# Main_Board.net
KiCad netlist of a schematic drawn in EAGLE
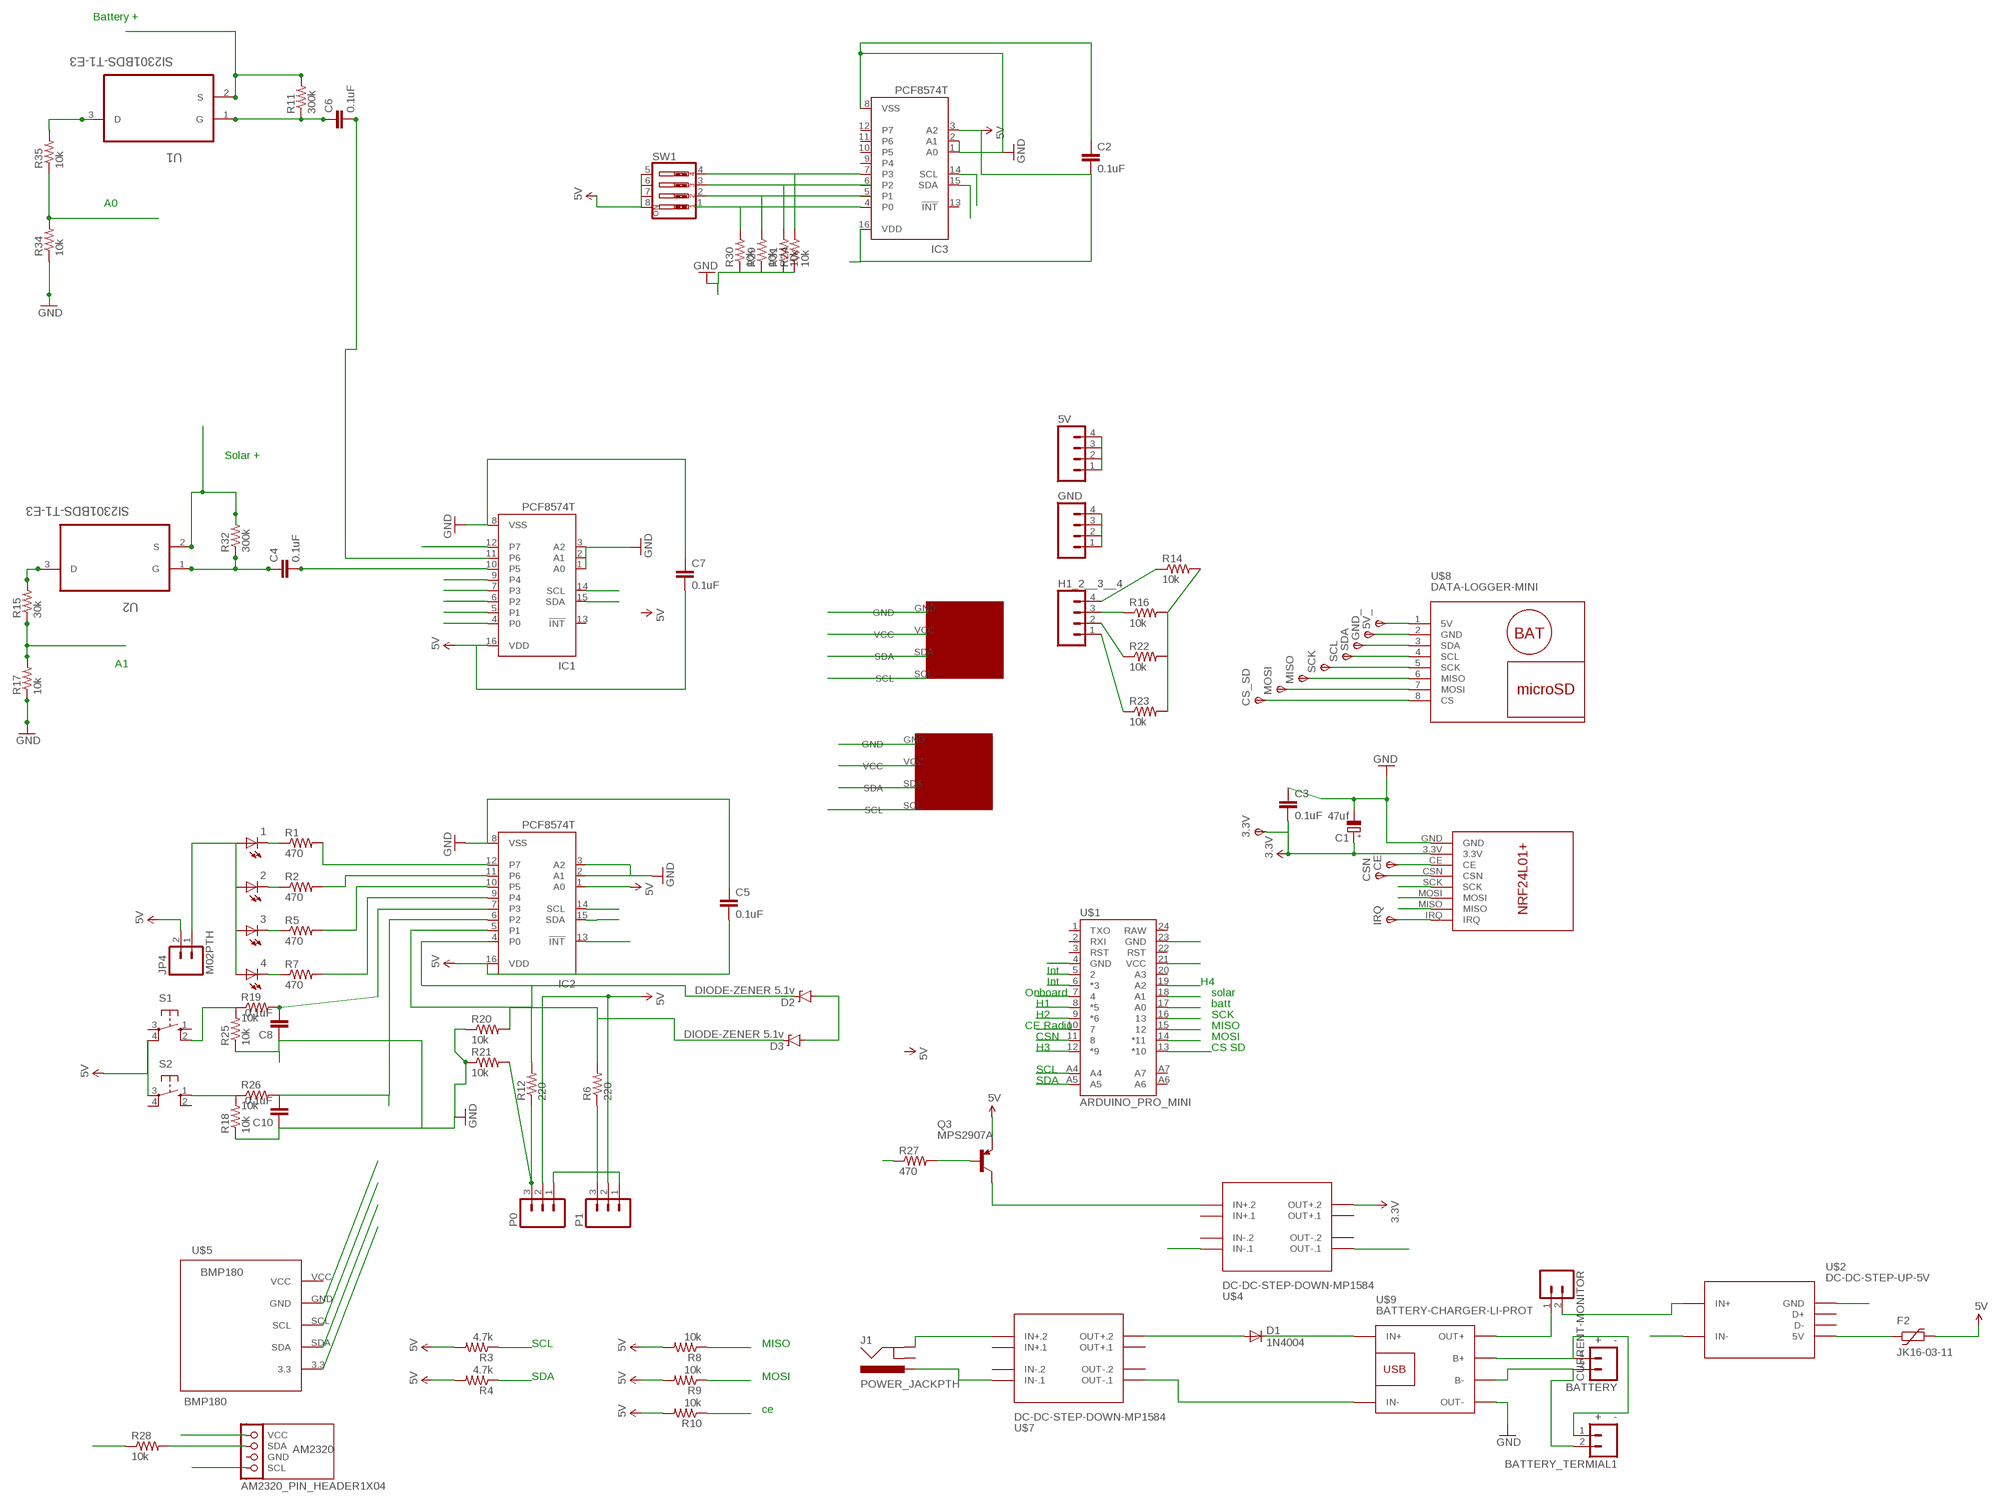
[diagram p0: schematic, sheet 1]

(export (version "E")
  (design (tool "Eeschema 10.0.6"))
  (components
    (comp (ref "1")
      (value "LED3MM")
      (footprint "eagle-import:LED3MM")
      (libsource (lib "eagle-import") (part "LED3MM"))
    )
    (comp (ref "2")
      (value "LED3MM")
      (footprint "eagle-import:LED3MM")
      (libsource (lib "eagle-import") (part "LED3MM"))
    )
    (comp (ref "3")
      (value "LED3MM")
      (footprint "eagle-import:LED3MM")
      (libsource (lib "eagle-import") (part "LED3MM"))
    )
    (comp (ref "3.3V")
      (value "TPSB1,27")
      (footprint "eagle-import:B1,27")
      (libsource (lib "eagle-import") (part "TPSB1,27"))
    )
    (comp (ref "4")
      (value "LED3MM")
      (footprint "eagle-import:LED3MM")
      (libsource (lib "eagle-import") (part "LED3MM"))
    )
    (comp (ref "5V")
      (value "M04PTH")
      (footprint "eagle-import:1X04")
      (libsource (lib "eagle-import") (part "M04PTH"))
    )
    (comp (ref "5V_")
      (value "SCK")
      (footprint "eagle-import:B1,27")
      (libsource (lib "eagle-import") (part "TPSB1,27"))
    )
    (comp (ref "AM2320")
      (value "AM2320_PIN_HEADER1X04")
      (footprint "eagle-import:1X04")
      (libsource (lib "eagle-import") (part "AM2320_PIN_HEADER1X04"))
    )
    (comp (ref "BATTERY")
      (value "+ -")
      (footprint "eagle-import:1X02")
      (libsource (lib "eagle-import") (part "M02PTH"))
    )
    (comp (ref "BATTERY_TERMIAL1")
      (value "+ -")
      (footprint "eagle-import:1X02")
      (libsource (lib "eagle-import") (part "M02PTH"))
    )
    (comp (ref "C1")
      (value "47uf")
      (footprint "eagle-import:E2,5-5")
      (libsource (lib "eagle-import") (part "CPOL-EUE2.5-5"))
    )
    (comp (ref "C2")
      (value "0.1uF")
      (footprint "eagle-import:0805")
      (libsource (lib "eagle-import") (part "2.2UF-25V-+80/-20(0805)"))
    )
    (comp (ref "C3")
      (value "0.1uF")
      (footprint "eagle-import:0805")
      (libsource (lib "eagle-import") (part "2.2UF-25V-+80/-20(0805)"))
    )
    (comp (ref "C4")
      (value "0.1uF")
      (footprint "eagle-import:0805")
      (libsource (lib "eagle-import") (part "2.2UF-25V-+80/-20(0805)"))
    )
    (comp (ref "C5")
      (value "0.1uF")
      (footprint "eagle-import:0805")
      (libsource (lib "eagle-import") (part "2.2UF-25V-+80/-20(0805)"))
    )
    (comp (ref "C6")
      (value "0.1uF")
      (footprint "eagle-import:0805")
      (libsource (lib "eagle-import") (part "2.2UF-25V-+80/-20(0805)"))
    )
    (comp (ref "C7")
      (value "0.1uF")
      (footprint "eagle-import:0805")
      (libsource (lib "eagle-import") (part "2.2UF-25V-+80/-20(0805)"))
    )
    (comp (ref "C8")
      (value "0.1uF")
      (footprint "eagle-import:0805")
      (libsource (lib "eagle-import") (part "2.2UF-25V-+80/-20(0805)"))
    )
    (comp (ref "C10")
      (value "0.1uF")
      (footprint "eagle-import:0805")
      (libsource (lib "eagle-import") (part "2.2UF-25V-+80/-20(0805)"))
    )
    (comp (ref "CE")
      (value "TPSB1,27")
      (footprint "eagle-import:B1,27")
      (libsource (lib "eagle-import") (part "TPSB1,27"))
    )
    (comp (ref "CSN")
      (value "TPSB1,27")
      (footprint "eagle-import:B1,27")
      (libsource (lib "eagle-import") (part "TPSB1,27"))
    )
    (comp (ref "CS_SD")
      (value "TPSB1,27")
      (footprint "eagle-import:B1,27")
      (libsource (lib "eagle-import") (part "TPSB1,27"))
    )
    (comp (ref "CURRENT-MONITOR")
      (value "M02PTH")
      (footprint "eagle-import:1X02")
      (libsource (lib "eagle-import") (part "M02PTH"))
    )
    (comp (ref "D1")
      (value "1N4004")
      (footprint "eagle-import:DO41-10")
      (libsource (lib "eagle-import") (part "1N4004"))
    )
    (comp (ref "D2")
      (value "DIODE-ZENER 5.1v")
      (footprint "eagle-import:DIODE-ZENER")
      (libsource (lib "eagle-import") (part "DIODE-ZENERPTH"))
    )
    (comp (ref "D3")
      (value "DIODE-ZENER 5.1v")
      (footprint "eagle-import:DIODE-ZENER")
      (libsource (lib "eagle-import") (part "DIODE-ZENERPTH"))
    )
    (comp (ref "F2")
      (value "JK16-03-11")
      (footprint "eagle-import:JK16-03-11")
      (libsource (lib "eagle-import") (part "JK16-03-11"))
    )
    (comp (ref "GND")
      (value "M04PTH")
      (footprint "eagle-import:1X04")
      (libsource (lib "eagle-import") (part "M04PTH"))
    )
    (comp (ref "GND_")
      (value "GND")
      (footprint "eagle-import:B1,27")
      (libsource (lib "eagle-import") (part "TPSB1,27"))
    )
    (comp (ref "H1_2__3__4")
      (value "M04PTH")
      (footprint "eagle-import:1X04")
      (libsource (lib "eagle-import") (part "M04PTH"))
    )
    (comp (ref "IC1")
      (value "PCF8574T")
      (footprint "eagle-import:SO16W")
      (fields (field (name "MPN") "PCF8574T/3,512"))
      (libsource (lib "eagle-import") (part "PCF8574T"))
    )
    (comp (ref "IC2")
      (value "PCF8574T")
      (footprint "eagle-import:SO16W")
      (fields (field (name "MPN") "PCF8574T/3,512"))
      (libsource (lib "eagle-import") (part "PCF8574T"))
    )
    (comp (ref "IC3")
      (value "PCF8574T")
      (footprint "eagle-import:SO16W")
      (fields (field (name "MPN") "PCF8574T/3,512"))
      (libsource (lib "eagle-import") (part "PCF8574T"))
    )
    (comp (ref "IRQ")
      (value "TPSB1,27")
      (footprint "eagle-import:B1,27")
      (libsource (lib "eagle-import") (part "TPSB1,27"))
    )
    (comp (ref "J1")
      (value "POWER_JACKPTH")
      (footprint "eagle-import:POWER_JACK_PTH")
      (libsource (lib "eagle-import") (part "POWER_JACKPTH"))
    )
    (comp (ref "JP4")
      (value "M02PTH")
      (footprint "eagle-import:1X02")
      (libsource (lib "eagle-import") (part "M02PTH"))
    )
    (comp (ref "MISO")
      (value "TPSB1,27")
      (footprint "eagle-import:B1,27")
      (libsource (lib "eagle-import") (part "TPSB1,27"))
    )
    (comp (ref "MOSI")
      (value "TPSB1,27")
      (footprint "eagle-import:B1,27")
      (libsource (lib "eagle-import") (part "TPSB1,27"))
    )
    (comp (ref "P0")
      (value "M03PTH")
      (footprint "eagle-import:1X03")
      (libsource (lib "eagle-import") (part "M03PTH"))
    )
    (comp (ref "P1")
      (value "M03PTH")
      (footprint "eagle-import:1X03")
      (libsource (lib "eagle-import") (part "M03PTH"))
    )
    (comp (ref "Q3")
      (value "MPS2907A")
      (footprint "eagle-import:TO92-CBE")
      (libsource (lib "eagle-import") (part "MPS2907A"))
    )
    (comp (ref "R1")
      (value "470")
      (footprint "eagle-import:1206")
      (libsource (lib "eagle-import") (part "RESISTOR1206"))
    )
    (comp (ref "R2")
      (value "470")
      (footprint "eagle-import:1206")
      (libsource (lib "eagle-import") (part "RESISTOR1206"))
    )
    (comp (ref "R3")
      (value "4.7k")
      (footprint "eagle-import:1206")
      (libsource (lib "eagle-import") (part "RESISTOR1206"))
    )
    (comp (ref "R4")
      (value "4.7k")
      (footprint "eagle-import:1206")
      (libsource (lib "eagle-import") (part "RESISTOR1206"))
    )
    (comp (ref "R5")
      (value "470")
      (footprint "eagle-import:1206")
      (libsource (lib "eagle-import") (part "RESISTOR1206"))
    )
    (comp (ref "R6")
      (value "220")
      (footprint "eagle-import:1206")
      (libsource (lib "eagle-import") (part "RESISTOR1206"))
    )
    (comp (ref "R7")
      (value "470")
      (footprint "eagle-import:1206")
      (libsource (lib "eagle-import") (part "RESISTOR1206"))
    )
    (comp (ref "R8")
      (value "10k")
      (footprint "eagle-import:1206")
      (libsource (lib "eagle-import") (part "RESISTOR1206"))
    )
    (comp (ref "R9")
      (value "10k")
      (footprint "eagle-import:1206")
      (libsource (lib "eagle-import") (part "RESISTOR1206"))
    )
    (comp (ref "R10")
      (value "10k")
      (footprint "eagle-import:1206")
      (libsource (lib "eagle-import") (part "RESISTOR1206"))
    )
    (comp (ref "R11")
      (value "300k")
      (footprint "eagle-import:1_6W-RES")
      (libsource (lib "eagle-import") (part "SparkFun-Resistors_RESISTORPTH-1/6W"))
    )
    (comp (ref "R12")
      (value "220")
      (footprint "eagle-import:1206")
      (libsource (lib "eagle-import") (part "RESISTOR1206"))
    )
    (comp (ref "R14")
      (value "10k")
      (footprint "eagle-import:1206")
      (libsource (lib "eagle-import") (part "RESISTOR1206"))
    )
    (comp (ref "R15")
      (value "30k")
      (footprint "eagle-import:1_6W-RES")
      (libsource (lib "eagle-import") (part "SparkFun-Resistors_RESISTORPTH-1/6W"))
    )
    (comp (ref "R16")
      (value "10k")
      (footprint "eagle-import:1206")
      (libsource (lib "eagle-import") (part "RESISTOR1206"))
    )
    (comp (ref "R17")
      (value "10k")
      (footprint "eagle-import:1_6W-RES")
      (libsource (lib "eagle-import") (part "SparkFun-Resistors_RESISTORPTH-1/6W"))
    )
    (comp (ref "R18")
      (value "10k")
      (footprint "eagle-import:1206")
      (libsource (lib "eagle-import") (part "RESISTOR1206"))
    )
    (comp (ref "R19")
      (value "10k")
      (footprint "eagle-import:1206")
      (libsource (lib "eagle-import") (part "RESISTOR1206"))
    )
    (comp (ref "R20")
      (value "10k")
      (footprint "eagle-import:1206")
      (libsource (lib "eagle-import") (part "SparkFun-Resistors_RESISTOR1206"))
    )
    (comp (ref "R21")
      (value "10k")
      (footprint "eagle-import:1206")
      (libsource (lib "eagle-import") (part "SparkFun-Resistors_RESISTOR1206"))
    )
    (comp (ref "R22")
      (value "10k")
      (footprint "eagle-import:1206")
      (libsource (lib "eagle-import") (part "RESISTOR1206"))
    )
    (comp (ref "R23")
      (value "10k")
      (footprint "eagle-import:1206")
      (libsource (lib "eagle-import") (part "RESISTOR1206"))
    )
    (comp (ref "R24")
      (value "10k")
      (footprint "eagle-import:1206")
      (libsource (lib "eagle-import") (part "RESISTOR1206"))
    )
    (comp (ref "R25")
      (value "10k")
      (footprint "eagle-import:1206")
      (libsource (lib "eagle-import") (part "RESISTOR1206"))
    )
    (comp (ref "R26")
      (value "10k")
      (footprint "eagle-import:1206")
      (libsource (lib "eagle-import") (part "RESISTOR1206"))
    )
    (comp (ref "R27")
      (value "470")
      (footprint "eagle-import:1206")
      (libsource (lib "eagle-import") (part "RESISTOR1206"))
    )
    (comp (ref "R28")
      (value "10k")
      (footprint "eagle-import:1206")
      (libsource (lib "eagle-import") (part "RESISTOR1206"))
    )
    (comp (ref "R29")
      (value "10k")
      (footprint "eagle-import:1206")
      (libsource (lib "eagle-import") (part "RESISTOR1206"))
    )
    (comp (ref "R30")
      (value "10k")
      (footprint "eagle-import:1206")
      (libsource (lib "eagle-import") (part "RESISTOR1206"))
    )
    (comp (ref "R31")
      (value "10k")
      (footprint "eagle-import:1206")
      (libsource (lib "eagle-import") (part "RESISTOR1206"))
    )
    (comp (ref "R32")
      (value "300k")
      (footprint "eagle-import:1_6W-RES")
      (libsource (lib "eagle-import") (part "SparkFun-Resistors_RESISTORPTH-1/6W"))
    )
    (comp (ref "R34")
      (value "10k")
      (footprint "eagle-import:1_6W-RES")
      (libsource (lib "eagle-import") (part "SparkFun-Resistors_RESISTORPTH-1/6W"))
    )
    (comp (ref "R35")
      (value "10k")
      (footprint "eagle-import:1_6W-RES")
      (libsource (lib "eagle-import") (part "SparkFun-Resistors_RESISTORPTH-1/6W"))
    )
    (comp (ref "S1")
      (value "10-XX")
      (footprint "eagle-import:B3F-10XX")
      (libsource (lib "eagle-import") (part "10-XX"))
    )
    (comp (ref "S2")
      (value "10-XX")
      (footprint "eagle-import:B3F-10XX")
      (libsource (lib "eagle-import") (part "10-XX"))
    )
    (comp (ref "SCK")
      (value "SCK")
      (footprint "eagle-import:B1,27")
      (libsource (lib "eagle-import") (part "TPSB1,27"))
    )
    (comp (ref "SCL")
      (value "SCK")
      (footprint "eagle-import:B1,27")
      (libsource (lib "eagle-import") (part "TPSB1,27"))
    )
    (comp (ref "SDA")
      (value "SCK")
      (footprint "eagle-import:B1,27")
      (libsource (lib "eagle-import") (part "TPSB1,27"))
    )
    (comp (ref "SW1")
      (value "SW_DIP-4")
      (footprint "eagle-import:EDG-04")
      (libsource (lib "eagle-import") (part "SW_DIP-4"))
    )
    (comp (ref "U$1")
      (value "ARDUINO_PRO_MINI")
      (footprint "eagle-import:ARDUINO_PRO_MINI")
      (libsource (lib "eagle-import") (part "ARDUINO_PRO_MINI"))
    )
    (comp (ref "U$2")
      (value "DC-DC-STEP-UP-5V")
      (footprint "eagle-import:DC-DC-STEP-UP-5V")
      (libsource (lib "eagle-import") (part "DC-DC-STEP-UP-5V"))
    )
    (comp (ref "U$3")
      (value "NRF24L01")
      (footprint "eagle-import:NRF24L01")
      (libsource (lib "eagle-import") (part "NRF24L01"))
    )
    (comp (ref "U$4")
      (value "DC-DC-STEP-DOWN-MP1584")
      (footprint "eagle-import:DC-DC-STEP-DOWN-MP1584")
      (libsource (lib "eagle-import") (part "DC-DC-STEP-DOWN-MP1584"))
    )
    (comp (ref "U$5")
      (value "BMP180")
      (footprint "eagle-import:1X05")
      (libsource (lib "eagle-import") (part "BMP180BMP180"))
    )
    (comp (ref "U$7")
      (value "DC-DC-STEP-DOWN-MP1584")
      (footprint "eagle-import:DC-DC-STEP-DOWN-MP1584")
      (libsource (lib "eagle-import") (part "DC-DC-STEP-DOWN-MP1584"))
    )
    (comp (ref "U$8")
      (value "DATA-LOGGER-MINI")
      (footprint "eagle-import:DATA-LOGGER-MINI")
      (libsource (lib "eagle-import") (part "DATA-LOGGER-MINI"))
    )
    (comp (ref "U$9")
      (value "BATTERY-CHARGER-LI-PROT")
      (footprint "eagle-import:BATTERY-CHARGER-LI-PROT")
      (libsource (lib "eagle-import") (part "BATTERY-CHARGER-LI-PROT"))
    )
    (comp (ref "U$10")
      (value "TJC8-4P")
      (footprint "eagle-import:TJC8-4P")
      (libsource (lib "eagle-import") (part "TJC8-4P"))
    )
    (comp (ref "U$11")
      (value "TJC8-4P")
      (footprint "eagle-import:TJC8-4P")
      (libsource (lib "eagle-import") (part "TJC8-4P"))
    )
    (comp (ref "U1")
      (value "SI2301BDS-T1-E3")
      (footprint "eagle-import:SOT95P237X112-3N")
      (libsource (lib "eagle-import") (part "SI2301BDS-T1-E3"))
    )
    (comp (ref "U2")
      (value "SI2301BDS-T1-E3")
      (footprint "eagle-import:SOT95P237X112-3N")
      (libsource (lib "eagle-import") (part "SI2301BDS-T1-E3"))
    )
  )
  (nets
    (net (code "1") (name "/12B") (class "Default")
      (node (ref "IC1") (pin "12") (pinfunction "P7_12") (pintype "bidirectional"))
      (node (ref "R27") (pin "1") (pinfunction "1_1") (pintype "passive"))
    )
    (net (code "2") (name "/A0") (class "Default")
      (node (ref "R34") (pin "2") (pinfunction "2_2") (pintype "passive"))
      (node (ref "R35") (pin "1") (pinfunction "1_1") (pintype "passive"))
      (node (ref "U$1") (pin "17") (pinfunction "A0_17") (pintype "bidirectional"))
    )
    (net (code "3") (name "/A1") (class "Default")
      (node (ref "R15") (pin "1") (pinfunction "1_1") (pintype "passive"))
      (node (ref "R17") (pin "2") (pinfunction "2_2") (pintype "passive"))
      (node (ref "U$1") (pin "18") (pinfunction "A1_18") (pintype "bidirectional"))
    )
    (net (code "4") (name "/B+") (class "Default")
      (node (ref "BATTERY") (pin "1") (pinfunction "1_1") (pintype "passive"))
      (node (ref "BATTERY_TERMIAL1") (pin "1") (pinfunction "1_1") (pintype "passive"))
      (node (ref "R11") (pin "2") (pinfunction "2_2") (pintype "passive"))
      (node (ref "U$9") (pin "B+") (pinfunction "B+_B+") (pintype "bidirectional"))
      (node (ref "U1") (pin "2") (pinfunction "S_2") (pintype "passive"))
    )
    (net (code "5") (name "/CE_RADIO") (class "Default")
      (node (ref "CE") (pin "TP") (pinfunction "PP_TP") (pintype "input"))
      (node (ref "R10") (pin "1") (pinfunction "1_1") (pintype "passive"))
      (node (ref "U$1") (pin "10") (pinfunction "7_10") (pintype "bidirectional"))
      (node (ref "U$3") (pin "CE") (pinfunction "CE_CE") (pintype "bidirectional"))
    )
    (net (code "6") (name "/CS-SD") (class "Default")
      (node (ref "CS_SD") (pin "TP") (pinfunction "PP_TP") (pintype "input"))
      (node (ref "U$1") (pin "13") (pinfunction "*10_13") (pintype "bidirectional"))
      (node (ref "U$8") (pin "8") (pinfunction "CS_8") (pintype "power_in"))
    )
    (net (code "7") (name "/H1") (class "Default")
      (node (ref "H1_2__3__4") (pin "1") (pinfunction "1_1") (pintype "passive"))
      (node (ref "IC1") (pin "5") (pinfunction "P1_5") (pintype "bidirectional"))
      (node (ref "R23") (pin "1") (pinfunction "1_1") (pintype "passive"))
      (node (ref "U$1") (pin "8") (pinfunction "*5_8") (pintype "bidirectional"))
    )
    (net (code "8") (name "/H2") (class "Default")
      (node (ref "H1_2__3__4") (pin "2") (pinfunction "2_2") (pintype "passive"))
      (node (ref "IC1") (pin "6") (pinfunction "P2_6") (pintype "bidirectional"))
      (node (ref "R22") (pin "1") (pinfunction "1_1") (pintype "passive"))
      (node (ref "U$1") (pin "9") (pinfunction "*6_9") (pintype "bidirectional"))
    )
    (net (code "9") (name "/H3") (class "Default")
      (node (ref "H1_2__3__4") (pin "3") (pinfunction "3_3") (pintype "passive"))
      (node (ref "IC1") (pin "7") (pinfunction "P3_7") (pintype "bidirectional"))
      (node (ref "R16") (pin "1") (pinfunction "1_1") (pintype "passive"))
      (node (ref "U$1") (pin "12") (pinfunction "*9_12") (pintype "bidirectional"))
    )
    (net (code "10") (name "/H4") (class "Default")
      (node (ref "H1_2__3__4") (pin "4") (pinfunction "4_4") (pintype "passive"))
      (node (ref "IC1") (pin "9") (pinfunction "P4_9") (pintype "bidirectional"))
      (node (ref "R14") (pin "1") (pinfunction "1_1") (pintype "passive"))
      (node (ref "U$1") (pin "19") (pinfunction "A2_19") (pintype "bidirectional"))
    )
    (net (code "11") (name "/INT8574") (class "Default")
      (node (ref "IC2") (pin "13") (pinfunction "~{INT}_13") (pintype "output"))
      (node (ref "U$1") (pin "6") (pinfunction "*3_6") (pintype "bidirectional"))
    )
    (net (code "12") (name "/IRQ") (class "Default")
      (node (ref "IRQ") (pin "TP") (pinfunction "PP_TP") (pintype "input"))
      (node (ref "U$1") (pin "5") (pinfunction "2_5") (pintype "bidirectional"))
      (node (ref "U$3") (pin "IRQ") (pinfunction "IRQ_IRQ") (pintype "bidirectional"))
    )
    (net (code "13") (name "/MISO") (class "Default")
      (node (ref "MISO") (pin "TP") (pinfunction "PP_TP") (pintype "input"))
      (node (ref "R8") (pin "1") (pinfunction "1_1") (pintype "passive"))
      (node (ref "U$1") (pin "15") (pinfunction "12_15") (pintype "bidirectional"))
      (node (ref "U$3") (pin "MISO") (pinfunction "MISO_MISO") (pintype "bidirectional"))
      (node (ref "U$8") (pin "6") (pinfunction "MISO_6") (pintype "bidirectional"))
    )
    (net (code "14") (name "/MOSI") (class "Default")
      (node (ref "MOSI") (pin "TP") (pinfunction "PP_TP") (pintype "input"))
      (node (ref "R9") (pin "1") (pinfunction "1_1") (pintype "passive"))
      (node (ref "U$1") (pin "14") (pinfunction "*11_14") (pintype "bidirectional"))
      (node (ref "U$3") (pin "MOSI") (pinfunction "MOSI_MOSI") (pintype "bidirectional"))
      (node (ref "U$8") (pin "7") (pinfunction "MOSI_7") (pintype "bidirectional"))
    )
    (net (code "15") (name "/ONBOARD") (class "Default")
      (node (ref "AM2320") (pin "2") (pinfunction "SDA_2") (pintype "passive"))
      (node (ref "IC1") (pin "4") (pinfunction "P0_4") (pintype "bidirectional"))
      (node (ref "R28") (pin "2") (pinfunction "2_2") (pintype "passive"))
      (node (ref "U$1") (pin "7") (pinfunction "4_7") (pintype "bidirectional"))
    )
    (net (code "16") (name "/S+") (class "Default")
      (node (ref "J1") (pin "GND") (pinfunction "GND_GND") (pintype "bidirectional"))
      (node (ref "R32") (pin "2") (pinfunction "2_2") (pintype "passive"))
      (node (ref "U$7") (pin "IN+.2") (pinfunction "IN+.2_IN+.2") (pintype "bidirectional"))
      (node (ref "U2") (pin "2") (pinfunction "S_2") (pintype "passive"))
    )
    (net (code "17") (name "/SCK") (class "Default")
      (node (ref "SCK") (pin "TP") (pinfunction "PP_TP") (pintype "input"))
      (node (ref "U$1") (pin "16") (pinfunction "13_16") (pintype "bidirectional"))
      (node (ref "U$3") (pin "SCK") (pinfunction "SCK_SCK") (pintype "bidirectional"))
      (node (ref "U$8") (pin "5") (pinfunction "SCK_5") (pintype "bidirectional"))
    )
    (net (code "18") (name "/SCL") (class "Default")
      (node (ref "IC1") (pin "14") (pinfunction "SCL_14") (pintype "input"))
      (node (ref "IC2") (pin "14") (pinfunction "SCL_14") (pintype "input"))
      (node (ref "IC3") (pin "14") (pinfunction "SCL_14") (pintype "input"))
      (node (ref "R3") (pin "1") (pinfunction "1_1") (pintype "passive"))
      (node (ref "SCL") (pin "TP") (pinfunction "PP_TP") (pintype "input"))
      (node (ref "U$1") (pin "A5") (pinfunction "A5_A5") (pintype "bidirectional"))
      (node (ref "U$10") (pin "SCL") (pinfunction "SCL_SCL") (pintype "bidirectional"))
      (node (ref "U$11") (pin "SCL") (pinfunction "SCL_SCL") (pintype "bidirectional"))
      (node (ref "U$5") (pin "SCL") (pinfunction "SCL_SCL") (pintype "bidirectional"))
      (node (ref "U$8") (pin "4") (pinfunction "SCL_4") (pintype "bidirectional"))
    )
    (net (code "19") (name "/SDA") (class "Default")
      (node (ref "IC1") (pin "15") (pinfunction "SDA_15") (pintype "bidirectional"))
      (node (ref "IC2") (pin "15") (pinfunction "SDA_15") (pintype "bidirectional"))
      (node (ref "IC3") (pin "15") (pinfunction "SDA_15") (pintype "bidirectional"))
      (node (ref "R4") (pin "1") (pinfunction "1_1") (pintype "passive"))
      (node (ref "SDA") (pin "TP") (pinfunction "PP_TP") (pintype "input"))
      (node (ref "U$1") (pin "A4") (pinfunction "A4_A4") (pintype "bidirectional"))
      (node (ref "U$10") (pin "SDA") (pinfunction "SDA_SDA") (pintype "bidirectional"))
      (node (ref "U$11") (pin "SDA") (pinfunction "SDA_SDA") (pintype "bidirectional"))
      (node (ref "U$5") (pin "SDA") (pinfunction "SDA_SDA") (pintype "bidirectional"))
      (node (ref "U$8") (pin "3") (pinfunction "SDA_3") (pintype "bidirectional"))
    )
    (net (code "20") (name "3.3V") (class "Default")
      (node (ref "3.3V") (pin "TP") (pinfunction "PP_TP") (pintype "input"))
      (node (ref "C1") (pin "+") (pinfunction "+_+") (pintype "passive"))
      (node (ref "C3") (pin "2") (pinfunction "2_2") (pintype "passive"))
      (node (ref "U$3") (pin "3.3V") (pinfunction "3.3V_3.3V") (pintype "bidirectional"))
      (node (ref "U$4") (pin "OUT+.2") (pinfunction "OUT+.2_OUT+.2") (pintype "bidirectional"))
      (node (ref "U$5") (pin "3.3") (pinfunction "3.3_3.3") (pintype "bidirectional"))
    )
    (net (code "21") (name "5V") (class "Default")
      (node (ref "5V") (pin "1") (pinfunction "1_1") (pintype "passive"))
      (node (ref "5V") (pin "2") (pinfunction "2_2") (pintype "passive"))
      (node (ref "5V") (pin "3") (pinfunction "3_3") (pintype "passive"))
      (node (ref "5V") (pin "4") (pinfunction "4_4") (pintype "passive"))
      (node (ref "5V_") (pin "TP") (pinfunction "PP_TP") (pintype "input"))
      (node (ref "AM2320") (pin "1") (pinfunction "VCC_1") (pintype "passive"))
      (node (ref "C2") (pin "2") (pinfunction "2_2") (pintype "passive"))
      (node (ref "C5") (pin "2") (pinfunction "2_2") (pintype "passive"))
      (node (ref "C7") (pin "2") (pinfunction "2_2") (pintype "passive"))
      (node (ref "F2") (pin "P$2") (pinfunction "2_P$2") (pintype "passive"))
      (node (ref "IC1") (pin "16") (pinfunction "VDD_16") (pintype "power_in"))
      (node (ref "IC2") (pin "1") (pinfunction "A0_1") (pintype "input"))
      (node (ref "IC2") (pin "16") (pinfunction "VDD_16") (pintype "power_in"))
      (node (ref "IC3") (pin "16") (pinfunction "VDD_16") (pintype "power_in"))
      (node (ref "IC3") (pin "3") (pinfunction "A2_3") (pintype "input"))
      (node (ref "JP4") (pin "2") (pinfunction "2_2") (pintype "passive"))
      (node (ref "P0") (pin "2") (pinfunction "2_2") (pintype "passive"))
      (node (ref "P1") (pin "2") (pinfunction "2_2") (pintype "passive"))
      (node (ref "Q3") (pin "E") (pinfunction "E_E") (pintype "passive"))
      (node (ref "R10") (pin "2") (pinfunction "2_2") (pintype "passive"))
      (node (ref "R14") (pin "2") (pinfunction "2_2") (pintype "passive"))
      (node (ref "R16") (pin "2") (pinfunction "2_2") (pintype "passive"))
      (node (ref "R22") (pin "2") (pinfunction "2_2") (pintype "passive"))
      (node (ref "R23") (pin "2") (pinfunction "2_2") (pintype "passive"))
      (node (ref "R28") (pin "1") (pinfunction "1_1") (pintype "passive"))
      (node (ref "R3") (pin "2") (pinfunction "2_2") (pintype "passive"))
      (node (ref "R4") (pin "2") (pinfunction "2_2") (pintype "passive"))
      (node (ref "R8") (pin "2") (pinfunction "2_2") (pintype "passive"))
      (node (ref "R9") (pin "2") (pinfunction "2_2") (pintype "passive"))
      (node (ref "S1") (pin "4") (pinfunction "P1_4") (pintype "passive"))
      (node (ref "S2") (pin "3") (pinfunction "P_3") (pintype "passive"))
      (node (ref "SW1") (pin "5") (pinfunction "5_5") (pintype "passive"))
      (node (ref "SW1") (pin "6") (pinfunction "6_6") (pintype "passive"))
      (node (ref "SW1") (pin "7") (pinfunction "7_7") (pintype "passive"))
      (node (ref "SW1") (pin "8") (pinfunction "8_8") (pintype "passive"))
      (node (ref "U$1") (pin "21") (pinfunction "VCC_21") (pintype "bidirectional"))
      (node (ref "U$10") (pin "VCC") (pinfunction "VCC_VCC") (pintype "bidirectional"))
      (node (ref "U$11") (pin "VCC") (pinfunction "VCC_VCC") (pintype "bidirectional"))
      (node (ref "U$8") (pin "1") (pinfunction "5V_1") (pintype "power_in"))
    )
    (net (code "22") (name "GND") (class "Default")
      (node (ref "AM2320") (pin "4") (pinfunction "SCL_4") (pintype "passive"))
      (node (ref "C1") (pin "-") (pinfunction "-_-") (pintype "passive"))
      (node (ref "C10") (pin "1") (pinfunction "1_1") (pintype "passive"))
      (node (ref "C2") (pin "1") (pinfunction "1_1") (pintype "passive"))
      (node (ref "C3") (pin "1") (pinfunction "1_1") (pintype "passive"))
      (node (ref "C5") (pin "1") (pinfunction "1_1") (pintype "passive"))
      (node (ref "C7") (pin "1") (pinfunction "1_1") (pintype "passive"))
      (node (ref "C8") (pin "1") (pinfunction "1_1") (pintype "passive"))
      (node (ref "D2") (pin "P$2") (pinfunction "A_P$2") (pintype "passive"))
      (node (ref "D3") (pin "P$2") (pinfunction "A_P$2") (pintype "passive"))
      (node (ref "GND") (pin "1") (pinfunction "1_1") (pintype "passive"))
      (node (ref "GND") (pin "2") (pinfunction "2_2") (pintype "passive"))
      (node (ref "GND") (pin "3") (pinfunction "3_3") (pintype "passive"))
      (node (ref "GND") (pin "4") (pinfunction "4_4") (pintype "passive"))
      (node (ref "GND_") (pin "TP") (pinfunction "PP_TP") (pintype "input"))
      (node (ref "IC1") (pin "1") (pinfunction "A0_1") (pintype "input"))
      (node (ref "IC1") (pin "2") (pinfunction "A1_2") (pintype "input"))
      (node (ref "IC1") (pin "3") (pinfunction "A2_3") (pintype "input"))
      (node (ref "IC1") (pin "8") (pinfunction "VSS_8") (pintype "power_in"))
      (node (ref "IC2") (pin "2") (pinfunction "A1_2") (pintype "input"))
      (node (ref "IC2") (pin "3") (pinfunction "A2_3") (pintype "input"))
      (node (ref "IC2") (pin "8") (pinfunction "VSS_8") (pintype "power_in"))
      (node (ref "IC3") (pin "1") (pinfunction "A0_1") (pintype "input"))
      (node (ref "IC3") (pin "2") (pinfunction "A1_2") (pintype "input"))
      (node (ref "IC3") (pin "8") (pinfunction "VSS_8") (pintype "power_in"))
      (node (ref "P0") (pin "1") (pinfunction "1_1") (pintype "passive"))
      (node (ref "P1") (pin "1") (pinfunction "1_1") (pintype "passive"))
      (node (ref "R17") (pin "1") (pinfunction "1_1") (pintype "passive"))
      (node (ref "R18") (pin "1") (pinfunction "1_1") (pintype "passive"))
      (node (ref "R20") (pin "1") (pinfunction "1_1") (pintype "passive"))
      (node (ref "R21") (pin "1") (pinfunction "1_1") (pintype "passive"))
      (node (ref "R24") (pin "1") (pinfunction "1_1") (pintype "passive"))
      (node (ref "R25") (pin "1") (pinfunction "1_1") (pintype "passive"))
      (node (ref "R29") (pin "1") (pinfunction "1_1") (pintype "passive"))
      (node (ref "R30") (pin "1") (pinfunction "1_1") (pintype "passive"))
      (node (ref "R31") (pin "1") (pinfunction "1_1") (pintype "passive"))
      (node (ref "R34") (pin "1") (pinfunction "1_1") (pintype "passive"))
      (node (ref "U$1") (pin "23") (pinfunction "GND_23") (pintype "bidirectional"))
      (node (ref "U$1") (pin "4") (pinfunction "GND_4") (pintype "bidirectional"))
      (node (ref "U$10") (pin "GND") (pinfunction "GND_GND") (pintype "bidirectional"))
      (node (ref "U$11") (pin "GND") (pinfunction "GND_GND") (pintype "bidirectional"))
      (node (ref "U$2") (pin "GND") (pinfunction "GND_GND") (pintype "bidirectional"))
      (node (ref "U$2") (pin "IN-") (pinfunction "IN-_IN-") (pintype "power_in"))
      (node (ref "U$3") (pin "GND") (pinfunction "GND_GND") (pintype "bidirectional"))
      (node (ref "U$4") (pin "IN-.1") (pinfunction "IN-.1_IN-.1") (pintype "bidirectional"))
      (node (ref "U$4") (pin "OUT-.1") (pinfunction "OUT-.1_OUT-.1") (pintype "bidirectional"))
      (node (ref "U$5") (pin "GND") (pinfunction "GND_GND") (pintype "bidirectional"))
      (node (ref "U$8") (pin "2") (pinfunction "GND_2") (pintype "power_in"))
      (node (ref "U$9") (pin "OUT-") (pinfunction "OUT-_OUT-") (pintype "bidirectional"))
    )
    (net (code "23") (name "Net-(1-C)") (class "Default")
      (node (ref "1") (pin "K") (pinfunction "C_K") (pintype "passive"))
      (node (ref "R1") (pin "1") (pinfunction "1_1") (pintype "passive"))
    )
    (net (code "24") (name "Net-(1-PadA)") (class "Default")
      (node (ref "1") (pin "A") (pinfunction "A_A") (pintype "passive"))
      (node (ref "2") (pin "A") (pinfunction "A_A") (pintype "passive"))
      (node (ref "3") (pin "A") (pinfunction "A_A") (pintype "passive"))
      (node (ref "4") (pin "A") (pinfunction "A_A") (pintype "passive"))
      (node (ref "JP4") (pin "1") (pinfunction "1_1") (pintype "passive"))
    )
    (net (code "25") (name "Net-(2-C)") (class "Default")
      (node (ref "2") (pin "K") (pinfunction "C_K") (pintype "passive"))
      (node (ref "R2") (pin "1") (pinfunction "1_1") (pintype "passive"))
    )
    (net (code "26") (name "Net-(3-C)") (class "Default")
      (node (ref "3") (pin "K") (pinfunction "C_K") (pintype "passive"))
      (node (ref "R5") (pin "1") (pinfunction "1_1") (pintype "passive"))
    )
    (net (code "27") (name "Net-(4-C)") (class "Default")
      (node (ref "4") (pin "K") (pinfunction "C_K") (pintype "passive"))
      (node (ref "R7") (pin "1") (pinfunction "1_1") (pintype "passive"))
    )
    (net (code "28") (name "Net-(BATTERY-Pad2)") (class "Default")
      (node (ref "BATTERY") (pin "2") (pinfunction "2_2") (pintype "passive"))
      (node (ref "BATTERY_TERMIAL1") (pin "2") (pinfunction "2_2") (pintype "passive"))
      (node (ref "U$9") (pin "B-") (pinfunction "B-_B-") (pintype "bidirectional"))
    )
    (net (code "29") (name "Net-(CSN-PP)") (class "Default")
      (node (ref "CSN") (pin "TP") (pinfunction "PP_TP") (pintype "input"))
      (node (ref "U$3") (pin "CSN") (pinfunction "CSN_CSN") (pintype "bidirectional"))
    )
    (net (code "30") (name "Net-(CURRENT-MONITOR-Pad1)") (class "Default")
      (node (ref "CURRENT-MONITOR") (pin "1") (pinfunction "1_1") (pintype "passive"))
      (node (ref "U$9") (pin "OUT+") (pinfunction "OUT+_OUT+") (pintype "bidirectional"))
    )
    (net (code "31") (name "Net-(CURRENT-MONITOR-Pad2)") (class "Default")
      (node (ref "CURRENT-MONITOR") (pin "2") (pinfunction "2_2") (pintype "passive"))
      (node (ref "U$2") (pin "IN+") (pinfunction "IN+_IN+") (pintype "power_in"))
    )
    (net (code "32") (name "Net-(D1-PadA)") (class "Default")
      (node (ref "D1") (pin "A") (pinfunction "A_A") (pintype "passive"))
      (node (ref "U$7") (pin "OUT+.2") (pinfunction "OUT+.2_OUT+.2") (pintype "bidirectional"))
    )
    (net (code "33") (name "Net-(D1-PadC)") (class "Default")
      (node (ref "D1") (pin "C") (pinfunction "C_C") (pintype "passive"))
      (node (ref "U$9") (pin "IN+") (pinfunction "IN+_IN+") (pintype "bidirectional"))
    )
    (net (code "34") (name "Net-(D2-C)") (class "Default")
      (node (ref "D2") (pin "P$1") (pinfunction "C_P$1") (pintype "passive"))
      (node (ref "IC2") (pin "4") (pinfunction "P0_4") (pintype "bidirectional"))
      (node (ref "IC2") (pin "5") (pinfunction "P1_5") (pintype "bidirectional"))
      (node (ref "R12") (pin "2") (pinfunction "2_2") (pintype "passive"))
    )
    (net (code "35") (name "Net-(D3-C)") (class "Default")
      (node (ref "D3") (pin "P$1") (pinfunction "C_P$1") (pintype "passive"))
      (node (ref "R20") (pin "2") (pinfunction "2_2") (pintype "passive"))
      (node (ref "R6") (pin "2") (pinfunction "2_2") (pintype "passive"))
    )
    (net (code "36") (name "Net-(F2-1)") (class "Default")
      (node (ref "F2") (pin "P$1") (pinfunction "1_P$1") (pintype "passive"))
      (node (ref "U$2") (pin "5V") (pinfunction "5V_5V") (pintype "bidirectional"))
    )
    (net (code "37") (name "Net-(IC1-P5)") (class "Default")
      (node (ref "C4") (pin "2") (pinfunction "2_2") (pintype "passive"))
      (node (ref "IC1") (pin "10") (pinfunction "P5_10") (pintype "bidirectional"))
    )
    (net (code "38") (name "Net-(IC1-P6)") (class "Default")
      (node (ref "C6") (pin "2") (pinfunction "2_2") (pintype "passive"))
      (node (ref "IC1") (pin "11") (pinfunction "P6_11") (pintype "bidirectional"))
    )
    (net (code "39") (name "Net-(IC2-P2)") (class "Default")
      (node (ref "C10") (pin "2") (pinfunction "2_2") (pintype "passive"))
      (node (ref "IC2") (pin "6") (pinfunction "P2_6") (pintype "bidirectional"))
      (node (ref "R26") (pin "2") (pinfunction "2_2") (pintype "passive"))
    )
    (net (code "40") (name "Net-(IC2-P3)") (class "Default")
      (node (ref "C8") (pin "2") (pinfunction "2_2") (pintype "passive"))
      (node (ref "IC2") (pin "7") (pinfunction "P3_7") (pintype "bidirectional"))
      (node (ref "R19") (pin "2") (pinfunction "2_2") (pintype "passive"))
    )
    (net (code "41") (name "Net-(IC2-P4)") (class "Default")
      (node (ref "IC2") (pin "9") (pinfunction "P4_9") (pintype "bidirectional"))
      (node (ref "R7") (pin "2") (pinfunction "2_2") (pintype "passive"))
    )
    (net (code "42") (name "Net-(IC2-P5)") (class "Default")
      (node (ref "IC2") (pin "10") (pinfunction "P5_10") (pintype "bidirectional"))
      (node (ref "R5") (pin "2") (pinfunction "2_2") (pintype "passive"))
    )
    (net (code "43") (name "Net-(IC2-P6)") (class "Default")
      (node (ref "IC2") (pin "11") (pinfunction "P6_11") (pintype "bidirectional"))
      (node (ref "R2") (pin "2") (pinfunction "2_2") (pintype "passive"))
    )
    (net (code "44") (name "Net-(IC2-P7)") (class "Default")
      (node (ref "IC2") (pin "12") (pinfunction "P7_12") (pintype "bidirectional"))
      (node (ref "R1") (pin "2") (pinfunction "2_2") (pintype "passive"))
    )
    (net (code "45") (name "Net-(IC3-P0)") (class "Default")
      (node (ref "IC3") (pin "4") (pinfunction "P0_4") (pintype "bidirectional"))
      (node (ref "R30") (pin "2") (pinfunction "2_2") (pintype "passive"))
    )
    (net (code "46") (name "Net-(IC3-P3)") (class "Default")
      (node (ref "IC3") (pin "7") (pinfunction "P3_7") (pintype "bidirectional"))
      (node (ref "R24") (pin "2") (pinfunction "2_2") (pintype "passive"))
      (node (ref "SW1") (pin "4") (pinfunction "4_4") (pintype "passive"))
    )
    (net (code "47") (name "Net-(J1-PadPWR)") (class "Default")
      (node (ref "J1") (pin "PWR") (pinfunction "PWR_PWR") (pintype "bidirectional"))
      (node (ref "U$7") (pin "IN-.1") (pinfunction "IN-.1_IN-.1") (pintype "bidirectional"))
    )
    (net (code "48") (name "Net-(P0-Pad3)") (class "Default")
      (node (ref "P0") (pin "3") (pinfunction "3_3") (pintype "passive"))
      (node (ref "R12") (pin "1") (pinfunction "1_1") (pintype "passive"))
      (node (ref "R21") (pin "2") (pinfunction "2_2") (pintype "passive"))
    )
    (net (code "49") (name "Net-(P1-Pad3)") (class "Default")
      (node (ref "P1") (pin "3") (pinfunction "3_3") (pintype "passive"))
      (node (ref "R6") (pin "1") (pinfunction "1_1") (pintype "passive"))
    )
    (net (code "50") (name "Net-(Q3-PadB)") (class "Default")
      (node (ref "Q3") (pin "B") (pinfunction "B_B") (pintype "passive"))
      (node (ref "R27") (pin "2") (pinfunction "2_2") (pintype "passive"))
    )
    (net (code "51") (name "Net-(Q3-PadC)") (class "Default")
      (node (ref "Q3") (pin "C") (pinfunction "C_C") (pintype "passive"))
      (node (ref "U$4") (pin "IN+.2") (pinfunction "IN+.2_IN+.2") (pintype "bidirectional"))
    )
    (net (code "52") (name "Net-(R29-Pad2)") (class "Default")
      (node (ref "R29") (pin "2") (pinfunction "2_2") (pintype "passive"))
      (node (ref "SW1") (pin "2") (pinfunction "2_2") (pintype "passive"))
    )
    (net (code "53") (name "Net-(R31-Pad2)") (class "Default")
      (node (ref "R31") (pin "2") (pinfunction "2_2") (pintype "passive"))
      (node (ref "SW1") (pin "3") (pinfunction "3_3") (pintype "passive"))
    )
    (net (code "54") (name "Net-(S1-S1)") (class "Default")
      (node (ref "R19") (pin "1") (pinfunction "1_1") (pintype "passive"))
      (node (ref "R25") (pin "2") (pinfunction "2_2") (pintype "passive"))
      (node (ref "S1") (pin "2") (pinfunction "S1_2") (pintype "passive"))
    )
    (net (code "55") (name "Net-(S2-S)") (class "Default")
      (node (ref "R18") (pin "2") (pinfunction "2_2") (pintype "passive"))
      (node (ref "R26") (pin "1") (pinfunction "1_1") (pintype "passive"))
      (node (ref "S2") (pin "1") (pinfunction "S_1") (pintype "passive"))
    )
    (net (code "56") (name "Net-(U$7-PadOUT-.1)") (class "Default")
      (node (ref "U$7") (pin "OUT-.1") (pinfunction "OUT-.1_OUT-.1") (pintype "bidirectional"))
      (node (ref "U$9") (pin "IN-") (pinfunction "IN-_IN-") (pintype "bidirectional"))
    )
    (net (code "57") (name "Net-(U1-D)") (class "Default")
      (node (ref "R35") (pin "2") (pinfunction "2_2") (pintype "passive"))
      (node (ref "U1") (pin "3") (pinfunction "D_3") (pintype "passive"))
    )
    (net (code "58") (name "Net-(U1-G)") (class "Default")
      (node (ref "C6") (pin "1") (pinfunction "1_1") (pintype "passive"))
      (node (ref "R11") (pin "1") (pinfunction "1_1") (pintype "passive"))
      (node (ref "U1") (pin "1") (pinfunction "G_1") (pintype "passive"))
    )
    (net (code "59") (name "Net-(U2-D)") (class "Default")
      (node (ref "R15") (pin "2") (pinfunction "2_2") (pintype "passive"))
      (node (ref "U2") (pin "3") (pinfunction "D_3") (pintype "passive"))
    )
    (net (code "60") (name "Net-(U2-G)") (class "Default")
      (node (ref "C4") (pin "1") (pinfunction "1_1") (pintype "passive"))
      (node (ref "R32") (pin "1") (pinfunction "1_1") (pintype "passive"))
      (node (ref "U2") (pin "1") (pinfunction "G_1") (pintype "passive"))
    )
    (net (code "61") (name "unconnected-(AM2320-GND-Pad3)") (class "Default")
      (node (ref "AM2320") (pin "3") (pinfunction "GND_3") (pintype "passive"))
    )
    (net (code "62") (name "unconnected-(IC1-~{INT}-Pad13)") (class "Default")
      (node (ref "IC1") (pin "13") (pinfunction "~{INT}_13") (pintype "output"))
    )
    (net (code "63") (name "unconnected-(IC3-P1-Pad5)") (class "Default")
      (node (ref "IC3") (pin "5") (pinfunction "P1_5") (pintype "bidirectional"))
    )
    (net (code "64") (name "unconnected-(IC3-P2-Pad6)") (class "Default")
      (node (ref "IC3") (pin "6") (pinfunction "P2_6") (pintype "bidirectional"))
    )
    (net (code "65") (name "unconnected-(IC3-P4-Pad9)") (class "Default")
      (node (ref "IC3") (pin "9") (pinfunction "P4_9") (pintype "bidirectional"))
    )
    (net (code "66") (name "unconnected-(IC3-P5-Pad10)") (class "Default")
      (node (ref "IC3") (pin "10") (pinfunction "P5_10") (pintype "bidirectional"))
    )
    (net (code "67") (name "unconnected-(IC3-P6-Pad11)") (class "Default")
      (node (ref "IC3") (pin "11") (pinfunction "P6_11") (pintype "bidirectional"))
    )
    (net (code "68") (name "unconnected-(IC3-P7-Pad12)") (class "Default")
      (node (ref "IC3") (pin "12") (pinfunction "P7_12") (pintype "bidirectional"))
    )
    (net (code "69") (name "unconnected-(IC3-~{INT}-Pad13)") (class "Default")
      (node (ref "IC3") (pin "13") (pinfunction "~{INT}_13") (pintype "output"))
    )
    (net (code "70") (name "unconnected-(J1-PadGNDBREAK)") (class "Default")
      (node (ref "J1") (pin "GNDBREAK") (pinfunction "GNDBREAK_GNDBREAK") (pintype "bidirectional"))
    )
    (net (code "71") (name "unconnected-(S1-P-Pad3)") (class "Default")
      (node (ref "S1") (pin "3") (pinfunction "P_3") (pintype "passive"))
    )
    (net (code "72") (name "unconnected-(S1-S-Pad1)") (class "Default")
      (node (ref "S1") (pin "1") (pinfunction "S_1") (pintype "passive"))
    )
    (net (code "73") (name "unconnected-(S2-P1-Pad4)") (class "Default")
      (node (ref "S2") (pin "4") (pinfunction "P1_4") (pintype "passive"))
    )
    (net (code "74") (name "unconnected-(S2-S1-Pad2)") (class "Default")
      (node (ref "S2") (pin "2") (pinfunction "S1_2") (pintype "passive"))
    )
    (net (code "75") (name "unconnected-(SW1-Pad1)") (class "Default")
      (node (ref "SW1") (pin "1") (pinfunction "1_1") (pintype "passive"))
    )
    (net (code "76") (name "unconnected-(U$1-8-Pad11)") (class "Default")
      (node (ref "U$1") (pin "11") (pinfunction "8_11") (pintype "bidirectional"))
    )
    (net (code "77") (name "unconnected-(U$1-A3-Pad20)") (class "Default")
      (node (ref "U$1") (pin "20") (pinfunction "A3_20") (pintype "bidirectional"))
    )
    (net (code "78") (name "unconnected-(U$1-PadA6)") (class "Default")
      (node (ref "U$1") (pin "A6") (pinfunction "A6_A6") (pintype "bidirectional"))
    )
    (net (code "79") (name "unconnected-(U$1-PadA7)") (class "Default")
      (node (ref "U$1") (pin "A7") (pinfunction "A7_A7") (pintype "bidirectional"))
    )
    (net (code "80") (name "unconnected-(U$1-RAW-Pad24)") (class "Default")
      (node (ref "U$1") (pin "24") (pinfunction "RAW_24") (pintype "bidirectional"))
    )
    (net (code "81") (name "unconnected-(U$1-RST-Pad3)") (class "Default")
      (node (ref "U$1") (pin "3") (pinfunction "RST_3") (pintype "bidirectional"))
    )
    (net (code "82") (name "unconnected-(U$1-RST-Pad22)") (class "Default")
      (node (ref "U$1") (pin "22") (pinfunction "RST_22") (pintype "bidirectional"))
    )
    (net (code "83") (name "unconnected-(U$1-RXI-Pad2)") (class "Default")
      (node (ref "U$1") (pin "2") (pinfunction "RXI_2") (pintype "bidirectional"))
    )
    (net (code "84") (name "unconnected-(U$1-TXO-Pad1)") (class "Default")
      (node (ref "U$1") (pin "1") (pinfunction "TXO_1") (pintype "bidirectional"))
    )
    (net (code "85") (name "unconnected-(U$2-PadD+)") (class "Default")
      (node (ref "U$2") (pin "D+") (pinfunction "D+_D+") (pintype "bidirectional"))
    )
    (net (code "86") (name "unconnected-(U$2-PadD-)") (class "Default")
      (node (ref "U$2") (pin "D-") (pinfunction "D-_D-") (pintype "bidirectional"))
    )
    (net (code "87") (name "unconnected-(U$4-PadIN+.1)") (class "Default")
      (node (ref "U$4") (pin "IN+.1") (pinfunction "IN+.1_IN+.1") (pintype "bidirectional"))
    )
    (net (code "88") (name "unconnected-(U$4-PadIN-.2)") (class "Default")
      (node (ref "U$4") (pin "IN-.2") (pinfunction "IN-.2_IN-.2") (pintype "bidirectional"))
    )
    (net (code "89") (name "unconnected-(U$4-PadOUT+.1)") (class "Default")
      (node (ref "U$4") (pin "OUT+.1") (pinfunction "OUT+.1_OUT+.1") (pintype "bidirectional"))
    )
    (net (code "90") (name "unconnected-(U$4-PadOUT-.2)") (class "Default")
      (node (ref "U$4") (pin "OUT-.2") (pinfunction "OUT-.2_OUT-.2") (pintype "bidirectional"))
    )
    (net (code "91") (name "unconnected-(U$5-PadVCC)") (class "Default")
      (node (ref "U$5") (pin "VCC") (pinfunction "VCC_VCC") (pintype "bidirectional"))
    )
    (net (code "92") (name "unconnected-(U$7-PadIN+.1)") (class "Default")
      (node (ref "U$7") (pin "IN+.1") (pinfunction "IN+.1_IN+.1") (pintype "bidirectional"))
    )
    (net (code "93") (name "unconnected-(U$7-PadIN-.2)") (class "Default")
      (node (ref "U$7") (pin "IN-.2") (pinfunction "IN-.2_IN-.2") (pintype "bidirectional"))
    )
    (net (code "94") (name "unconnected-(U$7-PadOUT+.1)") (class "Default")
      (node (ref "U$7") (pin "OUT+.1") (pinfunction "OUT+.1_OUT+.1") (pintype "bidirectional"))
    )
    (net (code "95") (name "unconnected-(U$7-PadOUT-.2)") (class "Default")
      (node (ref "U$7") (pin "OUT-.2") (pinfunction "OUT-.2_OUT-.2") (pintype "bidirectional"))
    )
  )
)
